# DD2088PoE_Daisy_Chain_USB.net
KiCad netlist of a schematic drawn in Altium Designer
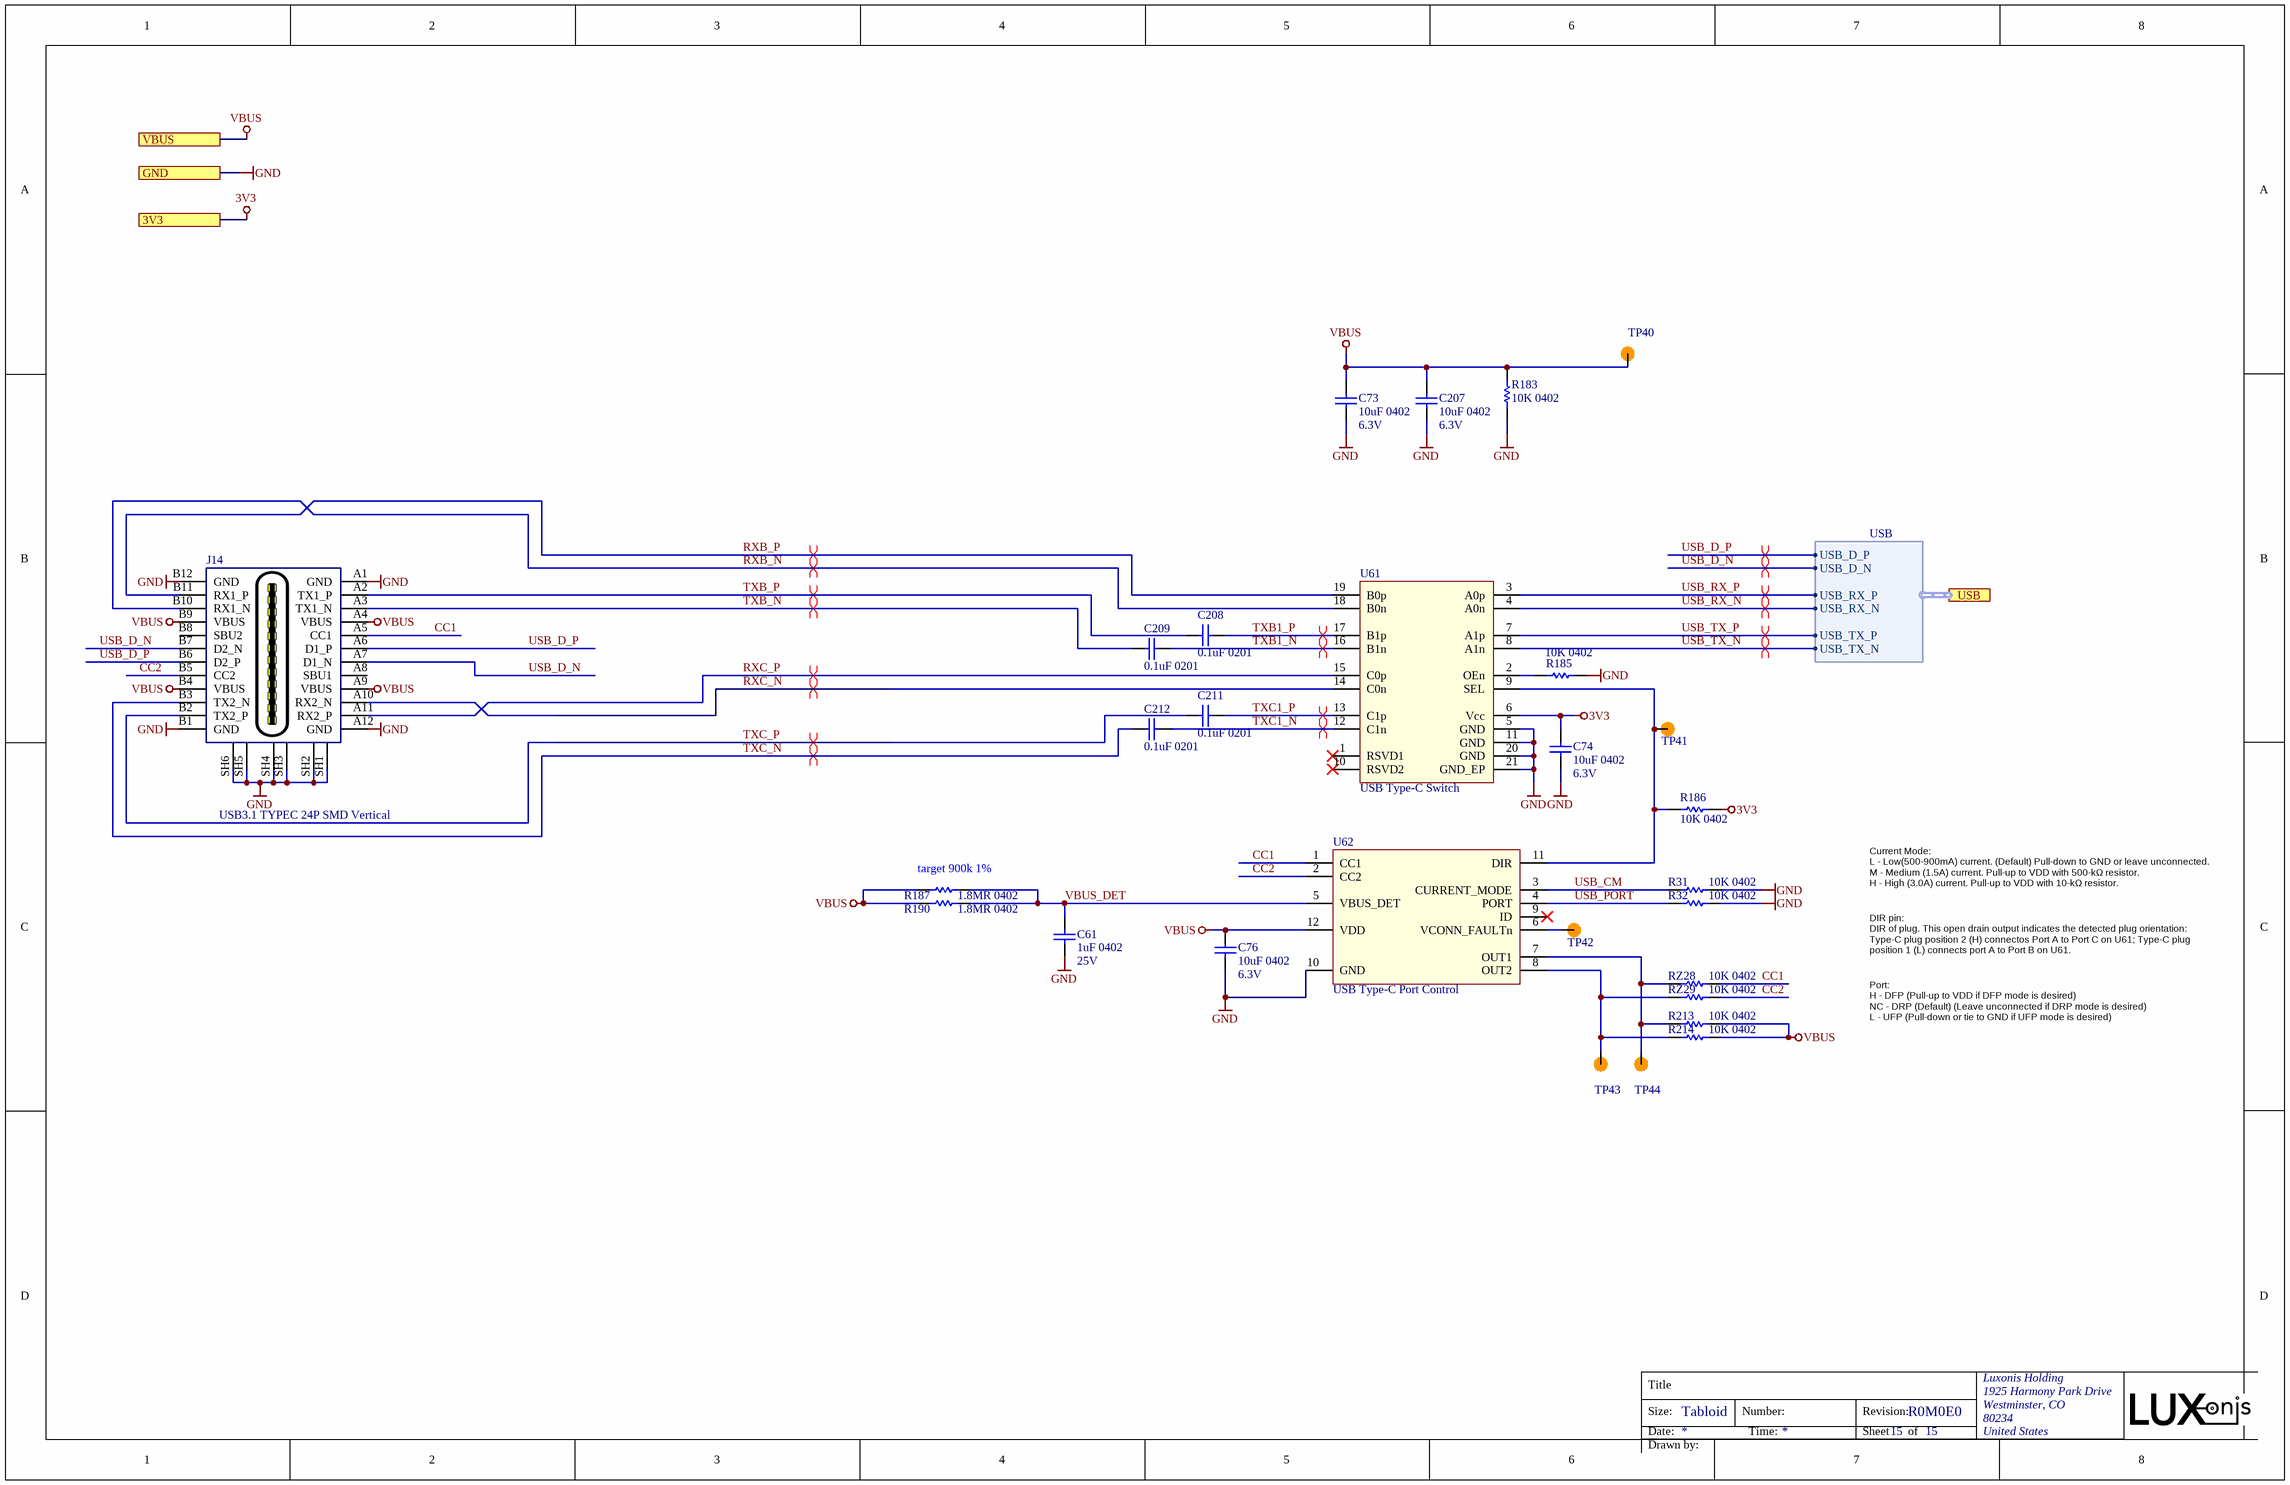
[diagram p0: DD2088PoE_Daisy_Chain_USB.SchDoc]

(export (version "E")
  (design (tool "Eeschema 10.0.6"))
  (components
    (comp (ref "C61")
      (value "1uF 0402")
      (footprint "CAP_Altium_Vault_Generic:CAPC0402(1005)70_N")
      (description "CAP CER 1UF 25V X5R 0402 10%")
      (fields
        (field (name "TOLERANCE") "10%")
        (field (name "VOLTAGE") "25V")
        (field (name "VOLTAGE RATING") "25V")
      )
      (libsource (lib "LuxonisMaster") (part "GRM155R61E105KA12D"))
    )
    (comp (ref "C73")
      (value "10uF 0402")
      (footprint "CAP_Altium_Vault_Generic:CAPC0402(1005)70_N")
      (description "CAP CER 10UF 6.3V X5R 0402 20%")
      (fields (field (name "TOLERANCE") "20%") (field (name "VOLTAGE RATING") "6.3V"))
      (libsource (lib "LuxonisMaster") (part "GRM155R60J106ME15D"))
    )
    (comp (ref "C74")
      (value "10uF 0402")
      (footprint "CAP_Altium_Vault_Generic:CAPC0402(1005)70_N")
      (description "CAP CER 10UF 6.3V X5R 0402 20%")
      (fields (field (name "TOLERANCE") "20%") (field (name "VOLTAGE RATING") "6.3V"))
      (libsource (lib "LuxonisMaster") (part "GRM155R60J106ME15D"))
    )
    (comp (ref "C76")
      (value "10uF 0402")
      (footprint "CAP_Altium_Vault_Generic:CAPC0402(1005)70_N")
      (description "CAP CER 10UF 6.3V X5R 0402 20%")
      (fields (field (name "TOLERANCE") "20%") (field (name "VOLTAGE RATING") "6.3V"))
      (libsource (lib "LuxonisMaster") (part "GRM155R60J106ME15D"))
    )
    (comp (ref "C207")
      (value "10uF 0402")
      (footprint "CAP_Altium_Vault_Generic:CAPC0402(1005)70_N")
      (description "CAP CER 10UF 6.3V X5R 0402 20%")
      (fields (field (name "TOLERANCE") "20%") (field (name "VOLTAGE RATING") "6.3V"))
      (libsource (lib "LuxonisMaster") (part "GRM155R60J106ME15D"))
    )
    (comp (ref "C208")
      (value "0.1uF 0201")
      (footprint "CAP_Altium_Vault_Generic:CAPC0201(0603)33_L")
      (description "CAP CER 0.1UF 10V X5R 0201")
      (fields (field (name "TOLERANCE") "10%") (field (name "VOLTAGE") "10V"))
      (libsource (lib "LuxonisMaster") (part "GRM033R61A104KE15D"))
    )
    (comp (ref "C209")
      (value "0.1uF 0201")
      (footprint "CAP_Altium_Vault_Generic:CAPC0201(0603)33_L")
      (description "CAP CER 0.1UF 10V X5R 0201")
      (fields (field (name "TOLERANCE") "10%") (field (name "VOLTAGE") "10V"))
      (libsource (lib "LuxonisMaster") (part "GRM033R61A104KE15D"))
    )
    (comp (ref "C211")
      (value "0.1uF 0201")
      (footprint "CAP_Altium_Vault_Generic:CAPC0201(0603)33_L")
      (description "CAP CER 0.1UF 10V X5R 0201")
      (fields (field (name "TOLERANCE") "10%") (field (name "VOLTAGE") "10V"))
      (libsource (lib "LuxonisMaster") (part "GRM033R61A104KE15D"))
    )
    (comp (ref "C212")
      (value "0.1uF 0201")
      (footprint "CAP_Altium_Vault_Generic:CAPC0201(0603)33_L")
      (description "CAP CER 0.1UF 10V X5R 0201")
      (fields (field (name "TOLERANCE") "10%") (field (name "VOLTAGE") "10V"))
      (libsource (lib "LuxonisMaster") (part "GRM033R61A104KE15D"))
    )
    (comp (ref "J14")
      (value "USB3.1 TYPEC 24P SMD Vertical")
      (footprint "SJ2088POE:CX80B1-24P")
      (description "CONN RCPT USB3.1 TYPEC 24POS SMD Vertical")
      (libsource (lib "SJ2088POE") (part "CX80B1-24P"))
    )
    (comp (ref "R31")
      (value "10K 0402")
      (footprint "RESC0402(1005)_N")
      (fields (field (name "TOLERANCE") "1%"))
      (libsource (lib "LuxonisMaster") (part "RC0402FR-1310KL"))
    )
    (comp (ref "R32")
      (value "10K 0402")
      (footprint "RESC0402(1005)_N")
      (fields (field (name "TOLERANCE") "1%"))
      (libsource (lib "LuxonisMaster") (part "RC0402FR-1310KL"))
    )
    (comp (ref "R183")
      (value "10K 0402")
      (footprint "RESC0402(1005)_N")
      (fields (field (name "TOLERANCE") "1%"))
      (libsource (lib "LuxonisMaster") (part "RC0402FR-1310KL"))
    )
    (comp (ref "R185")
      (value "10K 0402")
      (footprint "RESC0402(1005)_N")
      (fields (field (name "TOLERANCE") "1%"))
      (libsource (lib "LuxonisMaster") (part "RC0402FR-1310KL"))
    )
    (comp (ref "R186")
      (value "10K 0402")
      (footprint "RESC0402(1005)_N")
      (fields (field (name "TOLERANCE") "1%"))
      (libsource (lib "LuxonisMaster") (part "RC0402FR-1310KL"))
    )
    (comp (ref "R187")
      (value "1.8MR 0402")
      (footprint "RESC0402(1005)_N")
      (description "RES SMD 1.8M OHM 1% 1/16W 0402")
      (fields (field (name "TOLERANCE") "1%"))
      (libsource (lib "LuxonisMaster") (part "CRCW04021M80FKED"))
    )
    (comp (ref "R190")
      (value "1.8MR 0402")
      (footprint "RESC0402(1005)_N")
      (description "RES SMD 1.8M OHM 1% 1/16W 0402")
      (fields (field (name "TOLERANCE") "1%"))
      (libsource (lib "LuxonisMaster") (part "CRCW04021M80FKED"))
    )
    (comp (ref "R213")
      (value "10K 0402")
      (footprint "RESC0402(1005)_N")
      (fields (field (name "TOLERANCE") "1%"))
      (libsource (lib "LuxonisMaster") (part "RC0402FR-1310KL"))
    )
    (comp (ref "R214")
      (value "10K 0402")
      (footprint "RESC0402(1005)_N")
      (fields (field (name "TOLERANCE") "1%"))
      (libsource (lib "LuxonisMaster") (part "RC0402FR-1310KL"))
    )
    (comp (ref "RZ28")
      (value "10K 0402")
      (footprint "RESC0402(1005)_N")
      (fields (field (name "TOLERANCE") "1%"))
      (libsource (lib "LuxonisMaster") (part "RC0402FR-1310KL"))
    )
    (comp (ref "RZ29")
      (value "10K 0402")
      (footprint "RESC0402(1005)_N")
      (fields (field (name "TOLERANCE") "1%"))
      (libsource (lib "LuxonisMaster") (part "RC0402FR-1310KL"))
    )
    (comp (ref "TP40")
      (value "TP100_200_NS")
      (footprint "TP100_200_NS")
      (libsource (lib "LuxonisMaster") (part "TEST_POINT"))
    )
    (comp (ref "TP41")
      (value "TP100_200_NS")
      (footprint "TP100_200_NS")
      (libsource (lib "LuxonisMaster") (part "TEST_POINT"))
    )
    (comp (ref "TP42")
      (value "TP100_200_NS")
      (footprint "TP100_200_NS")
      (libsource (lib "LuxonisMaster") (part "TEST_POINT"))
    )
    (comp (ref "TP43")
      (value "TP100_200_NS")
      (footprint "TP100_200_NS")
      (libsource (lib "LuxonisMaster") (part "TEST_POINT"))
    )
    (comp (ref "TP44")
      (value "TP100_200_NS")
      (footprint "TP100_200_NS")
      (libsource (lib "LuxonisMaster") (part "TEST_POINT"))
    )
    (comp (ref "U61")
      (value "USB Type-C Switch")
      (footprint "LuxonisMaster:HD3SS3212RKSR")
      (description "IC MUX 2:1 8 OHM 20VQFN")
      (libsource (lib "LuxonisMaster") (part "HD3SS3212RKSR"))
    )
    (comp (ref "U62")
      (value "USB Type-C Port Control")
      (footprint "LuxonisMaster:TUSB321RWBR")
      (description "IC USB PORT CONTROL TYPE-C 12X2Q")
      (libsource (lib "LuxonisMaster") (part "TUSB321RWBR"))
    )
  )
  (nets
    (net (code "2") (name "/CC1") (class "Default")
      (node (ref "J14") (pin "A5") (pinfunction "CC1_A5") (pintype "passive"))
      (node (ref "RZ28") (pin "2") (pinfunction "2_2") (pintype "passive"))
      (node (ref "U62") (pin "1") (pinfunction "CC1_1") (pintype "passive"))
    )
    (net (code "3") (name "/CC2") (class "Default")
      (node (ref "J14") (pin "B5") (pinfunction "CC2_B5") (pintype "passive"))
      (node (ref "RZ29") (pin "2") (pinfunction "2_2") (pintype "passive"))
      (node (ref "U62") (pin "2") (pinfunction "CC2_2") (pintype "passive"))
    )
    (net (code "4") (name "/RXB_N") (class "Default")
      (node (ref "J14") (pin "B10") (pinfunction "RX1_N_B10") (pintype "passive"))
      (node (ref "U61") (pin "18") (pinfunction "B0n_18") (pintype "passive"))
    )
    (net (code "5") (name "/RXB_P") (class "Default")
      (node (ref "J14") (pin "B11") (pinfunction "RX1_P_B11") (pintype "passive"))
      (node (ref "U61") (pin "19") (pinfunction "B0p_19") (pintype "passive"))
    )
    (net (code "6") (name "/RXC_N") (class "Default")
      (node (ref "J14") (pin "A10") (pinfunction "RX2_N_A10") (pintype "passive"))
      (node (ref "U61") (pin "14") (pinfunction "C0n_14") (pintype "passive"))
    )
    (net (code "7") (name "/RXC_P") (class "Default")
      (node (ref "J14") (pin "A11") (pinfunction "RX2_P_A11") (pintype "passive"))
      (node (ref "U61") (pin "15") (pinfunction "C0p_15") (pintype "passive"))
    )
    (net (code "8") (name "/TXB1_N") (class "Default")
      (node (ref "C209") (pin "2") (pinfunction "2_2") (pintype "passive"))
      (node (ref "U61") (pin "16") (pinfunction "B1n_16") (pintype "passive"))
    )
    (net (code "9") (name "/TXB1_P") (class "Default")
      (node (ref "C208") (pin "2") (pinfunction "2_2") (pintype "passive"))
      (node (ref "U61") (pin "17") (pinfunction "B1p_17") (pintype "passive"))
    )
    (net (code "10") (name "/TXB_N") (class "Default")
      (node (ref "C209") (pin "1") (pinfunction "1_1") (pintype "passive"))
      (node (ref "J14") (pin "A3") (pinfunction "TX1_N_A3") (pintype "passive"))
    )
    (net (code "11") (name "/TXB_P") (class "Default")
      (node (ref "C208") (pin "1") (pinfunction "1_1") (pintype "passive"))
      (node (ref "J14") (pin "A2") (pinfunction "TX1_P_A2") (pintype "passive"))
    )
    (net (code "12") (name "/TXC1_N") (class "Default")
      (node (ref "C212") (pin "2") (pinfunction "2_2") (pintype "passive"))
      (node (ref "U61") (pin "12") (pinfunction "C1n_12") (pintype "passive"))
    )
    (net (code "13") (name "/TXC1_P") (class "Default")
      (node (ref "C211") (pin "2") (pinfunction "2_2") (pintype "passive"))
      (node (ref "U61") (pin "13") (pinfunction "C1p_13") (pintype "passive"))
    )
    (net (code "14") (name "/TXC_N") (class "Default")
      (node (ref "C212") (pin "1") (pinfunction "1_1") (pintype "passive"))
      (node (ref "J14") (pin "B3") (pinfunction "TX2_N_B3") (pintype "passive"))
    )
    (net (code "15") (name "/TXC_P") (class "Default")
      (node (ref "C211") (pin "1") (pinfunction "1_1") (pintype "passive"))
      (node (ref "J14") (pin "B2") (pinfunction "TX2_P_B2") (pintype "passive"))
    )
    (net (code "16") (name "/USB_CM") (class "Default")
      (node (ref "R31") (pin "1") (pinfunction "1_1") (pintype "passive"))
      (node (ref "U62") (pin "3") (pinfunction "CURRENT_MODE_3") (pintype "passive"))
    )
    (net (code "17") (name "/USB_D_N") (class "Default")
      (node (ref "J14") (pin "A7") (pinfunction "D1_N_A7") (pintype "passive"))
      (node (ref "J14") (pin "B7") (pinfunction "D2_N_B7") (pintype "passive"))
    )
    (net (code "18") (name "/USB_D_P") (class "Default")
      (node (ref "J14") (pin "A6") (pinfunction "D1_P_A6") (pintype "passive"))
      (node (ref "J14") (pin "B6") (pinfunction "D2_P_B6") (pintype "passive"))
    )
    (net (code "19") (name "/USB_PORT") (class "Default")
      (node (ref "R32") (pin "1") (pinfunction "1_1") (pintype "passive"))
      (node (ref "U62") (pin "4") (pinfunction "PORT_4") (pintype "passive"))
    )
    (net (code "20") (name "/USB_RX_N") (class "Default")
      (node (ref "U61") (pin "4") (pinfunction "A0n_4") (pintype "passive"))
    )
    (net (code "21") (name "/USB_RX_P") (class "Default")
      (node (ref "U61") (pin "3") (pinfunction "A0p_3") (pintype "passive"))
    )
    (net (code "22") (name "/USB_TX_N") (class "Default")
      (node (ref "U61") (pin "8") (pinfunction "A1n_8") (pintype "passive"))
    )
    (net (code "23") (name "/USB_TX_P") (class "Default")
      (node (ref "U61") (pin "7") (pinfunction "A1p_7") (pintype "passive"))
    )
    (net (code "24") (name "/VBUS_DET") (class "Default")
      (node (ref "C61") (pin "2") (pinfunction "2_2") (pintype "passive"))
      (node (ref "R187") (pin "2") (pinfunction "2_2") (pintype "passive"))
      (node (ref "R190") (pin "2") (pinfunction "2_2") (pintype "passive"))
      (node (ref "U62") (pin "5") (pinfunction "VBUS_DET_5") (pintype "passive"))
    )
    (net (code "26") (name "3V3") (class "Default")
      (node (ref "C74") (pin "2") (pinfunction "2_2") (pintype "passive"))
      (node (ref "R186") (pin "2") (pinfunction "2_2") (pintype "passive"))
      (node (ref "U61") (pin "6") (pinfunction "Vcc_6") (pintype "passive"))
    )
    (net (code "27") (name "GND") (class "Default")
      (node (ref "C207") (pin "1") (pinfunction "1_1") (pintype "passive"))
      (node (ref "C61") (pin "1") (pinfunction "1_1") (pintype "passive"))
      (node (ref "C73") (pin "1") (pinfunction "1_1") (pintype "passive"))
      (node (ref "C74") (pin "1") (pinfunction "1_1") (pintype "passive"))
      (node (ref "C76") (pin "1") (pinfunction "1_1") (pintype "passive"))
      (node (ref "J14") (pin "A1") (pinfunction "GND_A1") (pintype "passive"))
      (node (ref "J14") (pin "A12") (pinfunction "GND_A12") (pintype "passive"))
      (node (ref "J14") (pin "B1") (pinfunction "GND_B1") (pintype "passive"))
      (node (ref "J14") (pin "B12") (pinfunction "GND_B12") (pintype "passive"))
      (node (ref "J14") (pin "SH1") (pinfunction "SH_SH1") (pintype "passive"))
      (node (ref "J14") (pin "SH2") (pinfunction "SH_SH2") (pintype "passive"))
      (node (ref "J14") (pin "SH3") (pinfunction "SH_SH3") (pintype "passive"))
      (node (ref "J14") (pin "SH4") (pinfunction "SH_SH4") (pintype "passive"))
      (node (ref "J14") (pin "SH5") (pinfunction "SH_SH5") (pintype "passive"))
      (node (ref "J14") (pin "SH6") (pinfunction "SH_SH6") (pintype "passive"))
      (node (ref "R183") (pin "1") (pinfunction "1_1") (pintype "passive"))
      (node (ref "R185") (pin "2") (pinfunction "2_2") (pintype "passive"))
      (node (ref "R31") (pin "2") (pinfunction "2_2") (pintype "passive"))
      (node (ref "R32") (pin "2") (pinfunction "2_2") (pintype "passive"))
      (node (ref "U61") (pin "11") (pinfunction "GND_11") (pintype "passive"))
      (node (ref "U61") (pin "20") (pinfunction "GND_20") (pintype "passive"))
      (node (ref "U61") (pin "21") (pinfunction "GND_EP_21") (pintype "passive"))
      (node (ref "U61") (pin "5") (pinfunction "GND_5") (pintype "passive"))
      (node (ref "U62") (pin "10") (pinfunction "GND_10") (pintype "passive"))
    )
    (net (code "28") (name "Net-(U61-OEn)") (class "Default")
      (node (ref "R185") (pin "1") (pinfunction "1_1") (pintype "passive"))
      (node (ref "U61") (pin "2") (pinfunction "OEn_2") (pintype "passive"))
    )
    (net (code "29") (name "Net-(U61-SEL)") (class "Default")
      (node (ref "R186") (pin "1") (pinfunction "1_1") (pintype "passive"))
      (node (ref "TP41") (pin "1") (pintype "passive"))
      (node (ref "U61") (pin "9") (pinfunction "SEL_9") (pintype "passive"))
      (node (ref "U62") (pin "11") (pinfunction "DIR_11") (pintype "passive"))
    )
    (net (code "30") (name "Net-(U62-OUT1)") (class "Default")
      (node (ref "R213") (pin "1") (pinfunction "1_1") (pintype "passive"))
      (node (ref "RZ28") (pin "1") (pinfunction "1_1") (pintype "passive"))
      (node (ref "TP44") (pin "1") (pintype "passive"))
      (node (ref "U62") (pin "7") (pinfunction "OUT1_7") (pintype "passive"))
    )
    (net (code "31") (name "Net-(U62-OUT2)") (class "Default")
      (node (ref "R214") (pin "1") (pinfunction "1_1") (pintype "passive"))
      (node (ref "RZ29") (pin "1") (pinfunction "1_1") (pintype "passive"))
      (node (ref "TP43") (pin "1") (pintype "passive"))
      (node (ref "U62") (pin "8") (pinfunction "OUT2_8") (pintype "passive"))
    )
    (net (code "32") (name "Net-(U62-VCONN_FAULTn)") (class "Default")
      (node (ref "TP42") (pin "1") (pintype "passive"))
      (node (ref "U62") (pin "6") (pinfunction "VCONN_FAULTn_6") (pintype "passive"))
    )
    (net (code "33") (name "VBUS") (class "Default")
      (node (ref "C207") (pin "2") (pinfunction "2_2") (pintype "passive"))
      (node (ref "C73") (pin "2") (pinfunction "2_2") (pintype "passive"))
      (node (ref "C76") (pin "2") (pinfunction "2_2") (pintype "passive"))
      (node (ref "J14") (pin "A4") (pinfunction "VBUS_A4") (pintype "passive"))
      (node (ref "J14") (pin "A9") (pinfunction "VBUS_A9") (pintype "passive"))
      (node (ref "J14") (pin "B4") (pinfunction "VBUS_B4") (pintype "passive"))
      (node (ref "J14") (pin "B9") (pinfunction "VBUS_B9") (pintype "passive"))
      (node (ref "R183") (pin "2") (pinfunction "2_2") (pintype "passive"))
      (node (ref "R187") (pin "1") (pinfunction "1_1") (pintype "passive"))
      (node (ref "R190") (pin "1") (pinfunction "1_1") (pintype "passive"))
      (node (ref "R213") (pin "2") (pinfunction "2_2") (pintype "passive"))
      (node (ref "R214") (pin "2") (pinfunction "2_2") (pintype "passive"))
      (node (ref "TP40") (pin "1") (pintype "passive"))
      (node (ref "U62") (pin "12") (pinfunction "VDD_12") (pintype "passive"))
    )
    (net (code "34") (name "unconnected-(J14-SBU1-PadA8)") (class "Default")
      (node (ref "J14") (pin "A8") (pinfunction "SBU1_A8") (pintype "passive"))
    )
    (net (code "35") (name "unconnected-(J14-SBU2-PadB8)") (class "Default")
      (node (ref "J14") (pin "B8") (pinfunction "SBU2_B8") (pintype "passive"))
    )
    (net (code "36") (name "unconnected-(U61-RSVD1-Pad1)") (class "Default")
      (node (ref "U61") (pin "1") (pinfunction "RSVD1_1") (pintype "passive+no_connect"))
    )
    (net (code "37") (name "unconnected-(U61-RSVD2-Pad10)") (class "Default")
      (node (ref "U61") (pin "10") (pinfunction "RSVD2_10") (pintype "passive+no_connect"))
    )
    (net (code "38") (name "unconnected-(U62-ID-Pad9)") (class "Default")
      (node (ref "U62") (pin "9") (pinfunction "ID_9") (pintype "passive+no_connect"))
    )
  )
)
